# design.net
KiCad netlist of a schematic drawn in Altium Designer
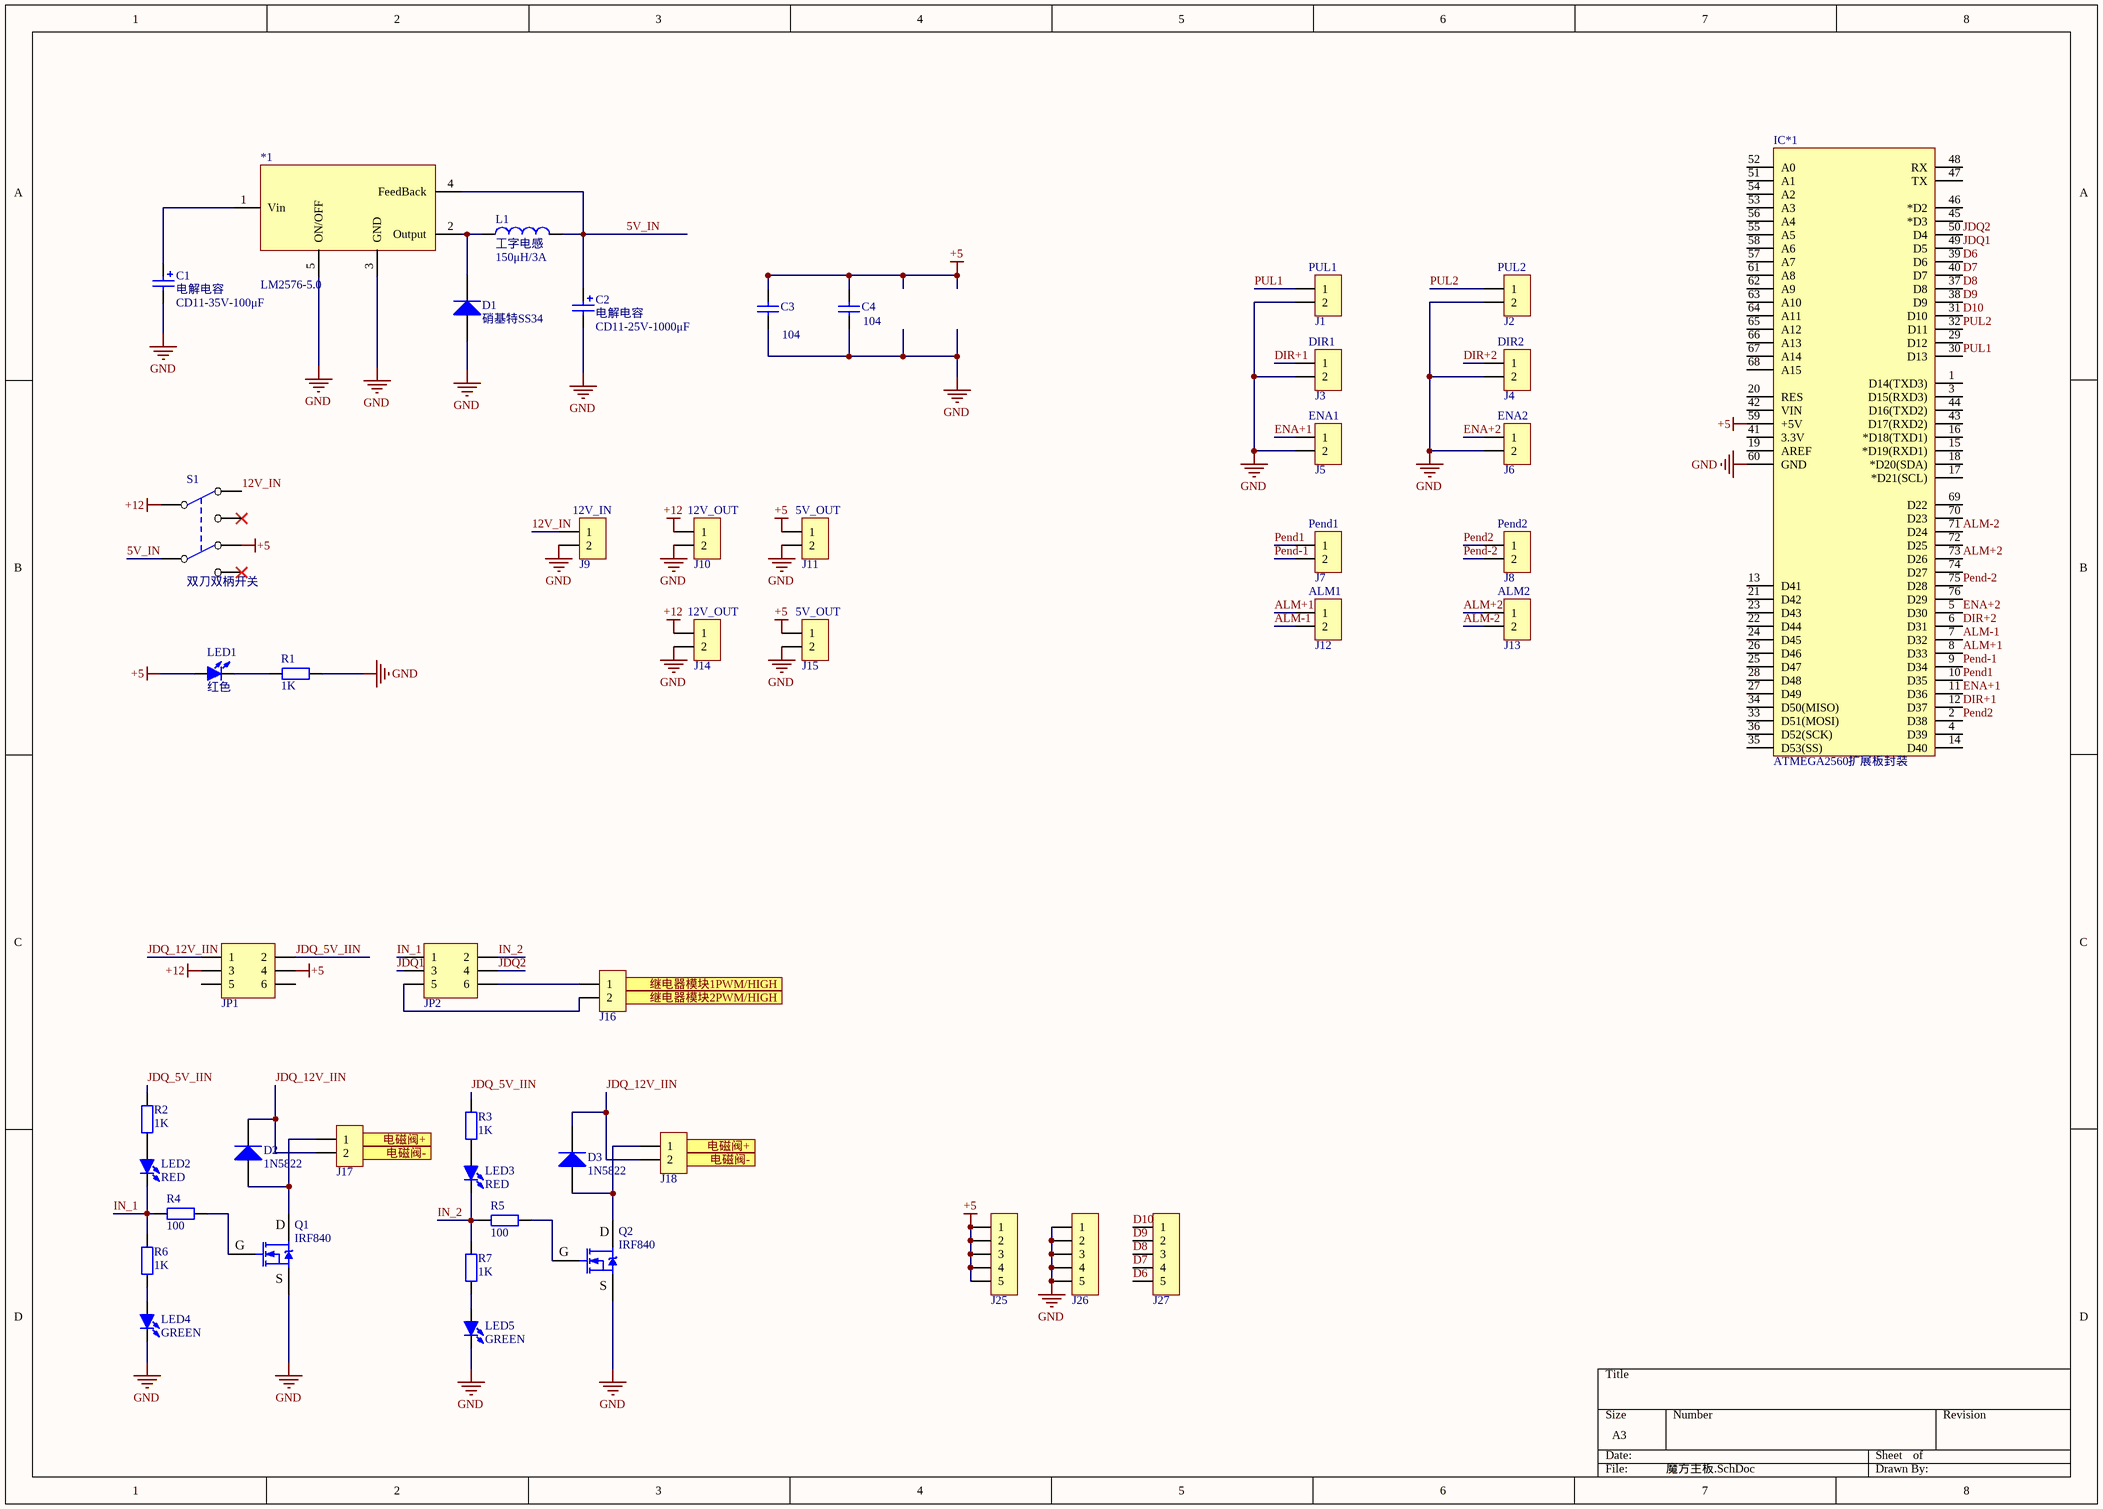
[diagram p0: 魔方主板.SchDoc]

(export (version "E")
  (design (tool "Eeschema 10.0.6"))
  (components
    (comp (ref "*1")
      (value "LM2576-5.0")
      (footprint "TO263-5")
      (libsource (lib "ATMEGA2560扩展原理图库v1.0") (part "LM2576HV-5.0"))
    )
    (comp (ref "C1")
      (value "电解电容")
      (footprint "CAP 3.5*8*11.5 - BK")
      (description "Polarized Capacitor (Axial)")
      (fields (field (name "ALTIUM_VALUE") "CD11-35V-100μF") (field (name "PUBLISHER") "Altium Limited"))
      (libsource (lib "Miscellaneous Devices") (part "Cap Pol2"))
    )
    (comp (ref "C2")
      (value "电解电容")
      (footprint "CAP 3.5*8*11.5")
      (description "Polarized Capacitor (Axial)")
      (fields (field (name "ALTIUM_VALUE") "CD11-25V-1000μF") (field (name "PUBLISHER") "Altium Limited"))
      (libsource (lib "Miscellaneous Devices") (part "Cap Pol2"))
    )
    (comp (ref "C3")
      (value "104")
      (footprint "C 0805_M")
      (description "Capacitor (Semiconductor SIM Model)")
      (fields (field (name "Comment") "104贴片电容") (field (name "PUBLISHER") "Altium Limited"))
      (libsource (lib "Miscellaneous Devices") (part "Cap Semi"))
    )
    (comp (ref "C4")
      (value "104")
      (footprint "C 0805_M")
      (description "Capacitor (Semiconductor SIM Model)")
      (fields (field (name "Comment") "104贴片电容") (field (name "PUBLISHER") "Altium Limited"))
      (libsource (lib "Miscellaneous Devices") (part "Cap Semi"))
    )
    (comp (ref "D1")
      (value "硝基特SS34")
      (footprint "SMB")
      (description "3 Amp Medium Power Silicon Rectifier Diode")
      (fields (field (name "PUBLISHER") "Altium Limited"))
      (libsource (lib "Miscellaneous Devices") (part "Diode 1N5408"))
    )
    (comp (ref "D2")
      (value "1N5822")
      (footprint "DO-201AD")
      (description "3 Amp Medium Power Silicon Rectifier Diode")
      (fields (field (name "PUBLISHER") "Altium Limited"))
      (libsource (lib "Miscellaneous Devices") (part "Diode 1N5408"))
    )
    (comp (ref "D3")
      (value "1N5822")
      (footprint "DO-201AD")
      (description "3 Amp Medium Power Silicon Rectifier Diode")
      (fields (field (name "PUBLISHER") "Altium Limited"))
      (libsource (lib "Miscellaneous Devices") (part "Diode 1N5408"))
    )
    (comp (ref "IC*1")
      (value "ATMEGA2560扩展板封装")
      (footprint "ATMEGA2560扩展板封装")
      (libsource (lib "ATMEGA2560") (part "ATMEGA2560扩展板封装"))
    )
    (comp (ref "J1")
      (value "PUL1")
      (footprint "KF128-5.08-2P")
      (description "2P接插件")
      (fields (field (name "版权归属") "源创客"))
      (libsource (lib "4.9   - 接插件-脚距5.0") (part "Header 2"))
    )
    (comp (ref "J2")
      (value "PUL2")
      (footprint "KF128-5.08-2P")
      (description "2P接插件")
      (fields (field (name "版权归属") "源创客"))
      (libsource (lib "4.9   - 接插件-脚距5.0") (part "Header 2"))
    )
    (comp (ref "J3")
      (value "DIR1")
      (footprint "KF128-5.08-2P")
      (description "2P接插件")
      (fields (field (name "版权归属") "源创客"))
      (libsource (lib "4.9   - 接插件-脚距5.0") (part "Header 2"))
    )
    (comp (ref "J4")
      (value "DIR2")
      (footprint "KF128-5.08-2P")
      (description "2P接插件")
      (fields (field (name "版权归属") "源创客"))
      (libsource (lib "4.9   - 接插件-脚距5.0") (part "Header 2"))
    )
    (comp (ref "J5")
      (value "ENA1")
      (footprint "KF128-5.08-2P")
      (description "2P接插件")
      (fields (field (name "版权归属") "源创客"))
      (libsource (lib "4.9   - 接插件-脚距5.0") (part "Header 2"))
    )
    (comp (ref "J6")
      (value "ENA2")
      (footprint "KF128-5.08-2P")
      (description "2P接插件")
      (fields (field (name "版权归属") "源创客"))
      (libsource (lib "4.9   - 接插件-脚距5.0") (part "Header 2"))
    )
    (comp (ref "J7")
      (value "Pend1")
      (footprint "KF128-5.08-2P")
      (description "2P接插件")
      (fields (field (name "版权归属") "源创客"))
      (libsource (lib "4.9   - 接插件-脚距5.0") (part "Header 2"))
    )
    (comp (ref "J8")
      (value "Pend2")
      (footprint "KF128-5.08-2P")
      (description "2P接插件")
      (fields (field (name "版权归属") "源创客"))
      (libsource (lib "4.9   - 接插件-脚距5.0") (part "Header 2"))
    )
    (comp (ref "J9")
      (value "12V_IN")
      (footprint "KF128-5.08-2P")
      (description "2P接插件")
      (fields (field (name "版权归属") "源创客"))
      (libsource (lib "4.9   - 接插件-脚距5.0") (part "Header 2"))
    )
    (comp (ref "J10")
      (value "12V_OUT")
      (footprint "KF128-5.08-2P")
      (description "2P接插件")
      (fields (field (name "版权归属") "源创客"))
      (libsource (lib "4.9   - 接插件-脚距5.0") (part "Header 2"))
    )
    (comp (ref "J11")
      (value "5V_OUT")
      (footprint "KF128-5.08-2P")
      (description "2P接插件")
      (fields (field (name "版权归属") "源创客"))
      (libsource (lib "4.9   - 接插件-脚距5.0") (part "Header 2"))
    )
    (comp (ref "J12")
      (value "ALM1")
      (footprint "KF128-5.08-2P")
      (description "2P接插件")
      (fields (field (name "版权归属") "源创客"))
      (libsource (lib "4.9   - 接插件-脚距5.0") (part "Header 2"))
    )
    (comp (ref "J13")
      (value "ALM2")
      (footprint "KF128-5.08-2P")
      (description "2P接插件")
      (fields (field (name "版权归属") "源创客"))
      (libsource (lib "4.9   - 接插件-脚距5.0") (part "Header 2"))
    )
    (comp (ref "J14")
      (value "12V_OUT")
      (footprint "KF128-5.08-2P")
      (description "2P接插件")
      (fields (field (name "版权归属") "源创客"))
      (libsource (lib "4.9   - 接插件-脚距5.0") (part "Header 2"))
    )
    (comp (ref "J15")
      (value "5V_OUT")
      (footprint "KF128-5.08-2P")
      (description "2P接插件")
      (fields (field (name "版权归属") "源创客"))
      (libsource (lib "4.9   - 接插件-脚距5.0") (part "Header 2"))
    )
    (comp (ref "J16")
      (value "HDR-1X2")
      (footprint "KF128-5.08-2P")
      (description "2P接插件")
      (fields (field (name "版权归属") "源创客"))
      (libsource (lib "4.9   - 接插件-脚距5.0") (part "Header 2"))
    )
    (comp (ref "J17")
      (value "HDR-1X2")
      (footprint "KF128-5.08-2P")
      (description "2P接插件")
      (fields (field (name "版权归属") "源创客"))
      (libsource (lib "4.9   - 接插件-脚距5.0") (part "Header 2"))
    )
    (comp (ref "J18")
      (value "HDR-1X2")
      (footprint "KF128-5.08-2P")
      (description "2P接插件")
      (fields (field (name "版权归属") "源创客"))
      (libsource (lib "4.9   - 接插件-脚距5.0") (part "Header 2"))
    )
    (comp (ref "J25")
      (value "HDR-1X5")
      (footprint "HDR2.54-LI-5P")
      (description "5P接插件")
      (fields (field (name "版权归属") "源创客"))
      (libsource (lib "4.5   - 接插件-脚距2.54") (part "Header 5"))
    )
    (comp (ref "J26")
      (value "HDR-1X5")
      (footprint "HDR2.54-LI-5P")
      (description "5P接插件")
      (fields (field (name "版权归属") "源创客"))
      (libsource (lib "4.5   - 接插件-脚距2.54") (part "Header 5"))
    )
    (comp (ref "J27")
      (value "HDR-1X5")
      (footprint "HDR2.54-LI-5P")
      (description "5P接插件")
      (fields (field (name "版权归属") "源创客"))
      (libsource (lib "4.5   - 接插件-脚距2.54") (part "Header 5"))
    )
    (comp (ref "JP1")
      (value "Header3X2")
      (footprint "HDR2.54-LI-2x3P")
      (description "3*2P接插件")
      (fields (field (name "版权归属") "源创客"))
      (libsource (lib "4.5   - 接插件-脚距2.54") (part "Header 3X2"))
    )
    (comp (ref "JP2")
      (value "Header3X2")
      (footprint "HDR2.54-LI-2x3P")
      (description "3*2P接插件")
      (fields (field (name "版权归属") "源创客"))
      (libsource (lib "4.5   - 接插件-脚距2.54") (part "Header 3X2"))
    )
    (comp (ref "L1")
      (value "工字电感")
      (footprint "PK0810")
      (description "Inductor")
      (fields (field (name "ALTIUM_VALUE") "150μH/3A") (field (name "PUBLISHER") "Altium Limited"))
      (libsource (lib "Miscellaneous Devices") (part "Inductor"))
    )
    (comp (ref "LED1")
      (value "红色")
      (footprint "LED 0805R")
      (description "贴片LED")
      (fields (field (name "版权归属") "源创客"))
      (libsource (lib "9.1   - LED") (part "LED-SMD"))
    )
    (comp (ref "LED2")
      (value "RED")
      (footprint "LED 0805R")
      (description "贴片LED")
      (fields (field (name "版权归属") "源创客"))
      (libsource (lib "9.1   - LED") (part "LED-SMD"))
    )
    (comp (ref "LED3")
      (value "RED")
      (footprint "LED 0805R")
      (description "贴片LED")
      (fields (field (name "版权归属") "源创客"))
      (libsource (lib "9.1   - LED") (part "LED-SMD"))
    )
    (comp (ref "LED4")
      (value "GREEN")
      (footprint "LED 0805R")
      (description "贴片LED")
      (fields (field (name "版权归属") "源创客"))
      (libsource (lib "9.1   - LED") (part "LED-SMD"))
    )
    (comp (ref "LED5")
      (value "GREEN")
      (footprint "LED 0805R")
      (description "贴片LED")
      (fields (field (name "版权归属") "源创客"))
      (libsource (lib "9.1   - LED") (part "LED-SMD"))
    )
    (comp (ref "Q1")
      (value "IRF840")
      (footprint "TO220A")
      (description "N沟场效应管")
      (fields (field (name "版权归属") "源创客"))
      (libsource (lib "6.1   - 场效应管-可控硅") (part "IRF840"))
    )
    (comp (ref "Q2")
      (value "IRF840")
      (footprint "TO220A")
      (description "N沟场效应管")
      (fields (field (name "版权归属") "源创客"))
      (libsource (lib "6.1   - 场效应管-可控硅") (part "IRF840"))
    )
    (comp (ref "R1")
      (value "1K")
      (footprint "R 0805_M")
      (description "贴片电阻")
      (fields (field (name "版权归属") "源创客"))
      (libsource (lib "电阻-电容-电感") (part "R"))
    )
    (comp (ref "R2")
      (value "1K")
      (footprint "R 0805_M")
      (description "贴片电阻")
      (fields (field (name "版权归属") "源创客"))
      (libsource (lib "电阻-电容-电感") (part "R"))
    )
    (comp (ref "R3")
      (value "1K")
      (footprint "R 0805_M")
      (description "贴片电阻")
      (fields (field (name "版权归属") "源创客"))
      (libsource (lib "电阻-电容-电感") (part "R"))
    )
    (comp (ref "R4")
      (value "100")
      (footprint "R 0805_M")
      (description "贴片电阻")
      (fields (field (name "版权归属") "源创客"))
      (libsource (lib "电阻-电容-电感") (part "R"))
    )
    (comp (ref "R5")
      (value "100")
      (footprint "R 0805_M")
      (description "贴片电阻")
      (fields (field (name "版权归属") "源创客"))
      (libsource (lib "电阻-电容-电感") (part "R"))
    )
    (comp (ref "R6")
      (value "1K")
      (footprint "R 0805_M")
      (description "贴片电阻")
      (fields (field (name "版权归属") "源创客"))
      (libsource (lib "电阻-电容-电感") (part "R"))
    )
    (comp (ref "R7")
      (value "1K")
      (footprint "R 0805_M")
      (description "贴片电阻")
      (fields (field (name "版权归属") "源创客"))
      (libsource (lib "电阻-电容-电感") (part "R"))
    )
    (comp (ref "S1") (value "双刀双柄开关") (footprint "双船开关") (libsource (lib "开关") (part "双刀双柄开关")))
  )
  (nets
    (net (code "1") (name "+5") (class "Default")
      (node (ref "C3") (pin "1") (pinfunction "1_1") (pintype "passive"))
      (node (ref "C4") (pin "1") (pinfunction "1_1") (pintype "passive"))
      (node (ref "IC*1") (pin "59") (pinfunction "+5V_59") (pintype "passive"))
      (node (ref "J11") (pin "1") (pinfunction "1_1") (pintype "passive"))
      (node (ref "J15") (pin "1") (pinfunction "1_1") (pintype "passive"))
      (node (ref "J25") (pin "1") (pinfunction "1_1") (pintype "passive"))
      (node (ref "J25") (pin "2") (pinfunction "2_2") (pintype "passive"))
      (node (ref "J25") (pin "3") (pinfunction "3_3") (pintype "passive"))
      (node (ref "J25") (pin "4") (pinfunction "4_4") (pintype "passive"))
      (node (ref "J25") (pin "5") (pinfunction "5_5") (pintype "passive"))
      (node (ref "JP1") (pin "4") (pinfunction "4_4") (pintype "passive"))
      (node (ref "LED1") (pin "1") (pinfunction "A_1") (pintype "passive"))
      (node (ref "S1") (pin "4") (pinfunction "NC2_4") (pintype "passive"))
    )
    (net (code "2") (name "+12") (class "Default")
      (node (ref "J10") (pin "1") (pinfunction "1_1") (pintype "passive"))
      (node (ref "J14") (pin "1") (pinfunction "1_1") (pintype "passive"))
      (node (ref "JP1") (pin "3") (pinfunction "3_3") (pintype "passive"))
      (node (ref "S1") (pin "1") (pinfunction "COMMON1_1") (pintype "passive"))
    )
    (net (code "3") (name "/5V_IN") (class "Default")
      (node (ref "*1") (pin "4") (pinfunction "FeedBack_4") (pintype "passive"))
      (node (ref "C2") (pin "1") (pinfunction "1_1") (pintype "passive"))
      (node (ref "L1") (pin "2") (pinfunction "2_2") (pintype "passive"))
      (node (ref "S1") (pin "5") (pinfunction "COMMON2_5") (pintype "passive"))
    )
    (net (code "4") (name "/12V_IN") (class "Default")
      (node (ref "J9") (pin "1") (pinfunction "1_1") (pintype "passive"))
      (node (ref "S1") (pin "2") (pinfunction "NC1_2") (pintype "passive"))
    )
    (net (code "5") (name "/ALM+1") (class "Default")
      (node (ref "IC*1") (pin "8") (pinfunction "D33_8") (pintype "passive"))
      (node (ref "J12") (pin "1") (pinfunction "1_1") (pintype "passive"))
    )
    (net (code "6") (name "/ALM+2") (class "Default")
      (node (ref "IC*1") (pin "73") (pinfunction "D26_73") (pintype "passive"))
      (node (ref "J13") (pin "1") (pinfunction "1_1") (pintype "passive"))
    )
    (net (code "7") (name "/ALM-1") (class "Default")
      (node (ref "IC*1") (pin "7") (pinfunction "D32_7") (pintype "passive"))
      (node (ref "J12") (pin "2") (pinfunction "2_2") (pintype "passive"))
    )
    (net (code "8") (name "/ALM-2") (class "Default")
      (node (ref "IC*1") (pin "71") (pinfunction "D24_71") (pintype "passive"))
      (node (ref "J13") (pin "2") (pinfunction "2_2") (pintype "passive"))
    )
    (net (code "9") (name "/D6") (class "Default")
      (node (ref "IC*1") (pin "39") (pinfunction "D6_39") (pintype "passive"))
      (node (ref "J27") (pin "5") (pinfunction "5_5") (pintype "passive"))
    )
    (net (code "10") (name "/D7") (class "Default")
      (node (ref "IC*1") (pin "40") (pinfunction "D7_40") (pintype "passive"))
      (node (ref "J27") (pin "4") (pinfunction "4_4") (pintype "passive"))
    )
    (net (code "11") (name "/D8") (class "Default")
      (node (ref "IC*1") (pin "37") (pinfunction "D8_37") (pintype "passive"))
      (node (ref "J27") (pin "3") (pinfunction "3_3") (pintype "passive"))
    )
    (net (code "12") (name "/D9") (class "Default")
      (node (ref "IC*1") (pin "38") (pinfunction "D9_38") (pintype "passive"))
      (node (ref "J27") (pin "2") (pinfunction "2_2") (pintype "passive"))
    )
    (net (code "13") (name "/D10") (class "Default")
      (node (ref "IC*1") (pin "31") (pinfunction "D10_31") (pintype "passive"))
      (node (ref "J27") (pin "1") (pinfunction "1_1") (pintype "passive"))
    )
    (net (code "14") (name "/DIR+1") (class "Default")
      (node (ref "IC*1") (pin "12") (pinfunction "D37_12") (pintype "passive"))
      (node (ref "J3") (pin "1") (pinfunction "1_1") (pintype "passive"))
    )
    (net (code "15") (name "/DIR+2") (class "Default")
      (node (ref "IC*1") (pin "6") (pinfunction "D31_6") (pintype "passive"))
      (node (ref "J4") (pin "1") (pinfunction "1_1") (pintype "passive"))
    )
    (net (code "16") (name "/ENA+1") (class "Default")
      (node (ref "IC*1") (pin "11") (pinfunction "D36_11") (pintype "passive"))
      (node (ref "J5") (pin "1") (pinfunction "1_1") (pintype "passive"))
    )
    (net (code "17") (name "/ENA+2") (class "Default")
      (node (ref "IC*1") (pin "5") (pinfunction "D30_5") (pintype "passive"))
      (node (ref "J6") (pin "1") (pinfunction "1_1") (pintype "passive"))
    )
    (net (code "18") (name "/IN_1") (class "Default")
      (node (ref "JP2") (pin "1") (pinfunction "1_1") (pintype "passive"))
      (node (ref "LED2") (pin "2") (pinfunction "K_2") (pintype "passive"))
      (node (ref "R4") (pin "2") (pinfunction "2_2") (pintype "passive"))
      (node (ref "R6") (pin "2") (pinfunction "2_2") (pintype "passive"))
    )
    (net (code "19") (name "/IN_2") (class "Default")
      (node (ref "JP2") (pin "2") (pinfunction "2_2") (pintype "passive"))
      (node (ref "LED3") (pin "2") (pinfunction "K_2") (pintype "passive"))
      (node (ref "R5") (pin "2") (pinfunction "2_2") (pintype "passive"))
      (node (ref "R7") (pin "2") (pinfunction "2_2") (pintype "passive"))
    )
    (net (code "20") (name "/JDQ1") (class "Default")
      (node (ref "IC*1") (pin "49") (pinfunction "D5_49") (pintype "passive"))
      (node (ref "JP2") (pin "3") (pinfunction "3_3") (pintype "passive"))
    )
    (net (code "21") (name "/JDQ2") (class "Default")
      (node (ref "IC*1") (pin "50") (pinfunction "D4_50") (pintype "passive"))
      (node (ref "JP2") (pin "4") (pinfunction "4_4") (pintype "passive"))
    )
    (net (code "22") (name "/JDQ_5V_IIN") (class "Default")
      (node (ref "JP1") (pin "2") (pinfunction "2_2") (pintype "passive"))
      (node (ref "R2") (pin "2") (pinfunction "2_2") (pintype "passive"))
      (node (ref "R3") (pin "2") (pinfunction "2_2") (pintype "passive"))
    )
    (net (code "23") (name "/JDQ_12V_IIN") (class "Default")
      (node (ref "D2") (pin "2") (pinfunction "K_2") (pintype "passive"))
      (node (ref "D3") (pin "2") (pinfunction "K_2") (pintype "passive"))
      (node (ref "J17") (pin "2") (pinfunction "2_2") (pintype "passive"))
      (node (ref "J18") (pin "2") (pinfunction "2_2") (pintype "passive"))
      (node (ref "JP1") (pin "1") (pinfunction "1_1") (pintype "passive"))
    )
    (net (code "24") (name "/PUL1") (class "Default")
      (node (ref "IC*1") (pin "30") (pinfunction "D13_30") (pintype "passive"))
      (node (ref "J1") (pin "1") (pinfunction "1_1") (pintype "passive"))
    )
    (net (code "25") (name "/PUL2") (class "Default")
      (node (ref "IC*1") (pin "32") (pinfunction "D11_32") (pintype "passive"))
      (node (ref "J2") (pin "1") (pinfunction "1_1") (pintype "passive"))
    )
    (net (code "26") (name "/Pend-1") (class "Default")
      (node (ref "IC*1") (pin "9") (pinfunction "D34_9") (pintype "passive"))
      (node (ref "J7") (pin "2") (pinfunction "2_2") (pintype "passive"))
    )
    (net (code "27") (name "/Pend-2") (class "Default")
      (node (ref "IC*1") (pin "75") (pinfunction "D28_75") (pintype "passive"))
      (node (ref "J8") (pin "2") (pinfunction "2_2") (pintype "passive"))
    )
    (net (code "28") (name "/Pend1") (class "Default")
      (node (ref "IC*1") (pin "10") (pinfunction "D35_10") (pintype "passive"))
      (node (ref "J7") (pin "1") (pinfunction "1_1") (pintype "passive"))
    )
    (net (code "29") (name "/Pend2") (class "Default")
      (node (ref "IC*1") (pin "2") (pinfunction "D38_2") (pintype "passive"))
      (node (ref "J8") (pin "1") (pinfunction "1_1") (pintype "passive"))
    )
    (net (code "34") (name "GND") (class "Default")
      (node (ref "*1") (pin "3") (pinfunction "GND_3") (pintype "passive"))
      (node (ref "*1") (pin "5") (pinfunction "ON/OFF_5") (pintype "passive"))
      (node (ref "C1") (pin "2") (pinfunction "2_2") (pintype "passive"))
      (node (ref "C2") (pin "2") (pinfunction "2_2") (pintype "passive"))
      (node (ref "C3") (pin "2") (pinfunction "2_2") (pintype "passive"))
      (node (ref "C4") (pin "2") (pinfunction "2_2") (pintype "passive"))
      (node (ref "D1") (pin "1") (pinfunction "A_1") (pintype "passive"))
      (node (ref "IC*1") (pin "60") (pinfunction "GND_60") (pintype "passive"))
      (node (ref "J1") (pin "2") (pinfunction "2_2") (pintype "passive"))
      (node (ref "J10") (pin "2") (pinfunction "2_2") (pintype "passive"))
      (node (ref "J11") (pin "2") (pinfunction "2_2") (pintype "passive"))
      (node (ref "J14") (pin "2") (pinfunction "2_2") (pintype "passive"))
      (node (ref "J15") (pin "2") (pinfunction "2_2") (pintype "passive"))
      (node (ref "J2") (pin "2") (pinfunction "2_2") (pintype "passive"))
      (node (ref "J26") (pin "1") (pinfunction "1_1") (pintype "passive"))
      (node (ref "J26") (pin "2") (pinfunction "2_2") (pintype "passive"))
      (node (ref "J26") (pin "3") (pinfunction "3_3") (pintype "passive"))
      (node (ref "J26") (pin "4") (pinfunction "4_4") (pintype "passive"))
      (node (ref "J26") (pin "5") (pinfunction "5_5") (pintype "passive"))
      (node (ref "J3") (pin "2") (pinfunction "2_2") (pintype "passive"))
      (node (ref "J4") (pin "2") (pinfunction "2_2") (pintype "passive"))
      (node (ref "J5") (pin "2") (pinfunction "2_2") (pintype "passive"))
      (node (ref "J6") (pin "2") (pinfunction "2_2") (pintype "passive"))
      (node (ref "J9") (pin "2") (pinfunction "2_2") (pintype "passive"))
      (node (ref "LED4") (pin "2") (pinfunction "K_2") (pintype "passive"))
      (node (ref "LED5") (pin "2") (pinfunction "K_2") (pintype "passive"))
      (node (ref "Q1") (pin "3") (pinfunction "S_3") (pintype "passive"))
      (node (ref "Q2") (pin "3") (pinfunction "S_3") (pintype "passive"))
      (node (ref "R1") (pin "1") (pinfunction "1_1") (pintype "passive"))
    )
    (net (code "35") (name "Net-(*1-Output)") (class "Default")
      (node (ref "*1") (pin "2") (pinfunction "Output_2") (pintype "passive"))
      (node (ref "D1") (pin "2") (pinfunction "K_2") (pintype "passive"))
      (node (ref "L1") (pin "1") (pinfunction "1_1") (pintype "passive"))
    )
    (net (code "36") (name "Net-(*1-Vin)") (class "Default")
      (node (ref "*1") (pin "1") (pinfunction "Vin_1") (pintype "passive"))
      (node (ref "C1") (pin "1") (pinfunction "1_1") (pintype "passive"))
    )
    (net (code "37") (name "Net-(D2-A)") (class "Default")
      (node (ref "D2") (pin "1") (pinfunction "A_1") (pintype "passive"))
      (node (ref "J17") (pin "1") (pinfunction "1_1") (pintype "passive"))
      (node (ref "Q1") (pin "2") (pinfunction "D_2") (pintype "passive"))
    )
    (net (code "38") (name "Net-(D3-A)") (class "Default")
      (node (ref "D3") (pin "1") (pinfunction "A_1") (pintype "passive"))
      (node (ref "J18") (pin "1") (pinfunction "1_1") (pintype "passive"))
      (node (ref "Q2") (pin "2") (pinfunction "D_2") (pintype "passive"))
    )
    (net (code "39") (name "Net-(J16-Pad1)") (class "Default")
      (node (ref "J16") (pin "1") (pinfunction "1_1") (pintype "passive"))
      (node (ref "JP2") (pin "6") (pinfunction "6_6") (pintype "passive"))
    )
    (net (code "40") (name "Net-(J16-Pad2)") (class "Default")
      (node (ref "J16") (pin "2") (pinfunction "2_2") (pintype "passive"))
      (node (ref "JP2") (pin "5") (pinfunction "5_5") (pintype "passive"))
    )
    (net (code "41") (name "Net-(LED1-K)") (class "Default")
      (node (ref "LED1") (pin "2") (pinfunction "K_2") (pintype "passive"))
      (node (ref "R1") (pin "2") (pinfunction "2_2") (pintype "passive"))
    )
    (net (code "42") (name "Net-(LED2-A)") (class "Default")
      (node (ref "LED2") (pin "1") (pinfunction "A_1") (pintype "passive"))
      (node (ref "R2") (pin "1") (pinfunction "1_1") (pintype "passive"))
    )
    (net (code "43") (name "Net-(LED3-A)") (class "Default")
      (node (ref "LED3") (pin "1") (pinfunction "A_1") (pintype "passive"))
      (node (ref "R3") (pin "1") (pinfunction "1_1") (pintype "passive"))
    )
    (net (code "44") (name "Net-(LED4-A)") (class "Default")
      (node (ref "LED4") (pin "1") (pinfunction "A_1") (pintype "passive"))
      (node (ref "R6") (pin "1") (pinfunction "1_1") (pintype "passive"))
    )
    (net (code "45") (name "Net-(LED5-A)") (class "Default")
      (node (ref "LED5") (pin "1") (pinfunction "A_1") (pintype "passive"))
      (node (ref "R7") (pin "1") (pinfunction "1_1") (pintype "passive"))
    )
    (net (code "46") (name "Net-(Q1-G)") (class "Default")
      (node (ref "Q1") (pin "1") (pinfunction "G_1") (pintype "passive"))
      (node (ref "R4") (pin "1") (pinfunction "1_1") (pintype "passive"))
    )
    (net (code "47") (name "Net-(Q2-G)") (class "Default")
      (node (ref "Q2") (pin "1") (pinfunction "G_1") (pintype "passive"))
      (node (ref "R5") (pin "1") (pinfunction "1_1") (pintype "passive"))
    )
    (net (code "48") (name "unconnected-(IC*1-*D2-Pad46)") (class "Default")
      (node (ref "IC*1") (pin "46") (pinfunction "*D2_46") (pintype "passive"))
    )
    (net (code "49") (name "unconnected-(IC*1-*D3-Pad45)") (class "Default")
      (node (ref "IC*1") (pin "45") (pinfunction "*D3_45") (pintype "passive"))
    )
    (net (code "50") (name "unconnected-(IC*1-*D18(TXD1)-Pad16)") (class "Default")
      (node (ref "IC*1") (pin "16") (pinfunction "*D18(TXD1)_16") (pintype "passive"))
    )
    (net (code "51") (name "unconnected-(IC*1-*D19(RXD1)-Pad15)") (class "Default")
      (node (ref "IC*1") (pin "15") (pinfunction "*D19(RXD1)_15") (pintype "passive"))
    )
    (net (code "52") (name "unconnected-(IC*1-*D20(SDA)-Pad18)") (class "Default")
      (node (ref "IC*1") (pin "18") (pinfunction "*D20(SDA)_18") (pintype "passive"))
    )
    (net (code "53") (name "unconnected-(IC*1-*D21(SCL)-Pad17)") (class "Default")
      (node (ref "IC*1") (pin "17") (pinfunction "*D21(SCL)_17") (pintype "passive"))
    )
    (net (code "54") (name "unconnected-(IC*1-3.3V-Pad41)") (class "Default")
      (node (ref "IC*1") (pin "41") (pinfunction "3.3V_41") (pintype "passive"))
    )
    (net (code "55") (name "unconnected-(IC*1-A0-Pad52)") (class "Default")
      (node (ref "IC*1") (pin "52") (pinfunction "A0_52") (pintype "passive"))
    )
    (net (code "56") (name "unconnected-(IC*1-A1-Pad51)") (class "Default")
      (node (ref "IC*1") (pin "51") (pinfunction "A1_51") (pintype "passive"))
    )
    (net (code "57") (name "unconnected-(IC*1-A2-Pad54)") (class "Default")
      (node (ref "IC*1") (pin "54") (pinfunction "A2_54") (pintype "passive"))
    )
    (net (code "58") (name "unconnected-(IC*1-A3-Pad53)") (class "Default")
      (node (ref "IC*1") (pin "53") (pinfunction "A3_53") (pintype "passive"))
    )
    (net (code "59") (name "unconnected-(IC*1-A4-Pad56)") (class "Default")
      (node (ref "IC*1") (pin "56") (pinfunction "A4_56") (pintype "passive"))
    )
    (net (code "60") (name "unconnected-(IC*1-A5-Pad55)") (class "Default")
      (node (ref "IC*1") (pin "55") (pinfunction "A5_55") (pintype "passive"))
    )
    (net (code "61") (name "unconnected-(IC*1-A6-Pad58)") (class "Default")
      (node (ref "IC*1") (pin "58") (pinfunction "A6_58") (pintype "passive"))
    )
    (net (code "62") (name "unconnected-(IC*1-A7-Pad57)") (class "Default")
      (node (ref "IC*1") (pin "57") (pinfunction "A7_57") (pintype "passive"))
    )
    (net (code "63") (name "unconnected-(IC*1-A8-Pad61)") (class "Default")
      (node (ref "IC*1") (pin "61") (pinfunction "A8_61") (pintype "passive"))
    )
    (net (code "64") (name "unconnected-(IC*1-A9-Pad62)") (class "Default")
      (node (ref "IC*1") (pin "62") (pinfunction "A9_62") (pintype "passive"))
    )
    (net (code "65") (name "unconnected-(IC*1-A10-Pad63)") (class "Default")
      (node (ref "IC*1") (pin "63") (pinfunction "A10_63") (pintype "passive"))
    )
    (net (code "66") (name "unconnected-(IC*1-A11-Pad64)") (class "Default")
      (node (ref "IC*1") (pin "64") (pinfunction "A11_64") (pintype "passive"))
    )
    (net (code "67") (name "unconnected-(IC*1-A12-Pad65)") (class "Default")
      (node (ref "IC*1") (pin "65") (pinfunction "A12_65") (pintype "passive"))
    )
    (net (code "68") (name "unconnected-(IC*1-A13-Pad66)") (class "Default")
      (node (ref "IC*1") (pin "66") (pinfunction "A13_66") (pintype "passive"))
    )
    (net (code "69") (name "unconnected-(IC*1-A14-Pad67)") (class "Default")
      (node (ref "IC*1") (pin "67") (pinfunction "A14_67") (pintype "passive"))
    )
    (net (code "70") (name "unconnected-(IC*1-A15-Pad68)") (class "Default")
      (node (ref "IC*1") (pin "68") (pinfunction "A15_68") (pintype "passive"))
    )
    (net (code "71") (name "unconnected-(IC*1-AREF-Pad19)") (class "Default")
      (node (ref "IC*1") (pin "19") (pinfunction "AREF_19") (pintype "passive"))
    )
    (net (code "72") (name "unconnected-(IC*1-D12-Pad29)") (class "Default")
      (node (ref "IC*1") (pin "29") (pinfunction "D12_29") (pintype "passive"))
    )
    (net (code "73") (name "unconnected-(IC*1-D14(TXD3)-Pad1)") (class "Default")
      (node (ref "IC*1") (pin "1") (pinfunction "D14(TXD3)_1") (pintype "passive"))
    )
    (net (code "74") (name "unconnected-(IC*1-D15(RXD3)-Pad3)") (class "Default")
      (node (ref "IC*1") (pin "3") (pinfunction "D15(RXD3)_3") (pintype "passive"))
    )
    (net (code "75") (name "unconnected-(IC*1-D16(TXD2)-Pad44)") (class "Default")
      (node (ref "IC*1") (pin "44") (pinfunction "D16(TXD2)_44") (pintype "passive"))
    )
    (net (code "76") (name "unconnected-(IC*1-D17(RXD2)-Pad43)") (class "Default")
      (node (ref "IC*1") (pin "43") (pinfunction "D17(RXD2)_43") (pintype "passive"))
    )
    (net (code "77") (name "unconnected-(IC*1-D22-Pad69)") (class "Default")
      (node (ref "IC*1") (pin "69") (pinfunction "D22_69") (pintype "passive"))
    )
    (net (code "78") (name "unconnected-(IC*1-D23-Pad70)") (class "Default")
      (node (ref "IC*1") (pin "70") (pinfunction "D23_70") (pintype "passive"))
    )
    (net (code "79") (name "unconnected-(IC*1-D25-Pad72)") (class "Default")
      (node (ref "IC*1") (pin "72") (pinfunction "D25_72") (pintype "passive"))
    )
    (net (code "80") (name "unconnected-(IC*1-D27-Pad74)") (class "Default")
      (node (ref "IC*1") (pin "74") (pinfunction "D27_74") (pintype "passive"))
    )
    (net (code "81") (name "unconnected-(IC*1-D29-Pad76)") (class "Default")
      (node (ref "IC*1") (pin "76") (pinfunction "D29_76") (pintype "passive"))
    )
    (net (code "82") (name "unconnected-(IC*1-D39-Pad4)") (class "Default")
      (node (ref "IC*1") (pin "4") (pinfunction "D39_4") (pintype "passive"))
    )
    (net (code "83") (name "unconnected-(IC*1-D40-Pad14)") (class "Default")
      (node (ref "IC*1") (pin "14") (pinfunction "D40_14") (pintype "passive"))
    )
    (net (code "84") (name "unconnected-(IC*1-D41-Pad13)") (class "Default")
      (node (ref "IC*1") (pin "13") (pinfunction "D41_13") (pintype "passive"))
    )
    (net (code "85") (name "unconnected-(IC*1-D42-Pad21)") (class "Default")
      (node (ref "IC*1") (pin "21") (pinfunction "D42_21") (pintype "passive"))
    )
    (net (code "86") (name "unconnected-(IC*1-D43-Pad23)") (class "Default")
      (node (ref "IC*1") (pin "23") (pinfunction "D43_23") (pintype "passive"))
    )
    (net (code "87") (name "unconnected-(IC*1-D44-Pad22)") (class "Default")
      (node (ref "IC*1") (pin "22") (pinfunction "D44_22") (pintype "passive"))
    )
    (net (code "88") (name "unconnected-(IC*1-D45-Pad24)") (class "Default")
      (node (ref "IC*1") (pin "24") (pinfunction "D45_24") (pintype "passive"))
    )
    (net (code "89") (name "unconnected-(IC*1-D46-Pad26)") (class "Default")
      (node (ref "IC*1") (pin "26") (pinfunction "D46_26") (pintype "passive"))
    )
    (net (code "90") (name "unconnected-(IC*1-D47-Pad25)") (class "Default")
      (node (ref "IC*1") (pin "25") (pinfunction "D47_25") (pintype "passive"))
    )
    (net (code "91") (name "unconnected-(IC*1-D48-Pad28)") (class "Default")
      (node (ref "IC*1") (pin "28") (pinfunction "D48_28") (pintype "passive"))
    )
    (net (code "92") (name "unconnected-(IC*1-D49-Pad27)") (class "Default")
      (node (ref "IC*1") (pin "27") (pinfunction "D49_27") (pintype "passive"))
    )
    (net (code "93") (name "unconnected-(IC*1-D50(MISO)-Pad34)") (class "Default")
      (node (ref "IC*1") (pin "34") (pinfunction "D50(MISO)_34") (pintype "passive"))
    )
    (net (code "94") (name "unconnected-(IC*1-D51(MOSI)-Pad33)") (class "Default")
      (node (ref "IC*1") (pin "33") (pinfunction "D51(MOSI)_33") (pintype "passive"))
    )
    (net (code "95") (name "unconnected-(IC*1-D52(SCK)-Pad36)") (class "Default")
      (node (ref "IC*1") (pin "36") (pinfunction "D52(SCK)_36") (pintype "passive"))
    )
    (net (code "96") (name "unconnected-(IC*1-D53(SS)-Pad35)") (class "Default")
      (node (ref "IC*1") (pin "35") (pinfunction "D53(SS)_35") (pintype "passive"))
    )
    (net (code "97") (name "unconnected-(IC*1-RES-Pad20)") (class "Default")
      (node (ref "IC*1") (pin "20") (pinfunction "RES_20") (pintype "passive"))
    )
    (net (code "98") (name "unconnected-(IC*1-RX-Pad48)") (class "Default")
      (node (ref "IC*1") (pin "48") (pinfunction "RX_48") (pintype "passive"))
    )
    (net (code "99") (name "unconnected-(IC*1-TX-Pad47)") (class "Default")
      (node (ref "IC*1") (pin "47") (pinfunction "TX_47") (pintype "passive"))
    )
    (net (code "100") (name "unconnected-(IC*1-VIN-Pad42)") (class "Default")
      (node (ref "IC*1") (pin "42") (pinfunction "VIN_42") (pintype "passive"))
    )
    (net (code "101") (name "unconnected-(JP1-Pad5)") (class "Default")
      (node (ref "JP1") (pin "5") (pinfunction "5_5") (pintype "passive"))
    )
    (net (code "102") (name "unconnected-(JP1-Pad6)") (class "Default")
      (node (ref "JP1") (pin "6") (pinfunction "6_6") (pintype "passive"))
    )
    (net (code "103") (name "unconnected-(S1-NO1-Pad3)") (class "Default")
      (node (ref "S1") (pin "3") (pinfunction "NO1_3") (pintype "passive+no_connect"))
    )
    (net (code "104") (name "unconnected-(S1-NO2-Pad6)") (class "Default")
      (node (ref "S1") (pin "6") (pinfunction "NO2_6") (pintype "passive+no_connect"))
    )
  )
)
